# tin_of_fets.net
KiCad netlist of a schematic drawn in EAGLE
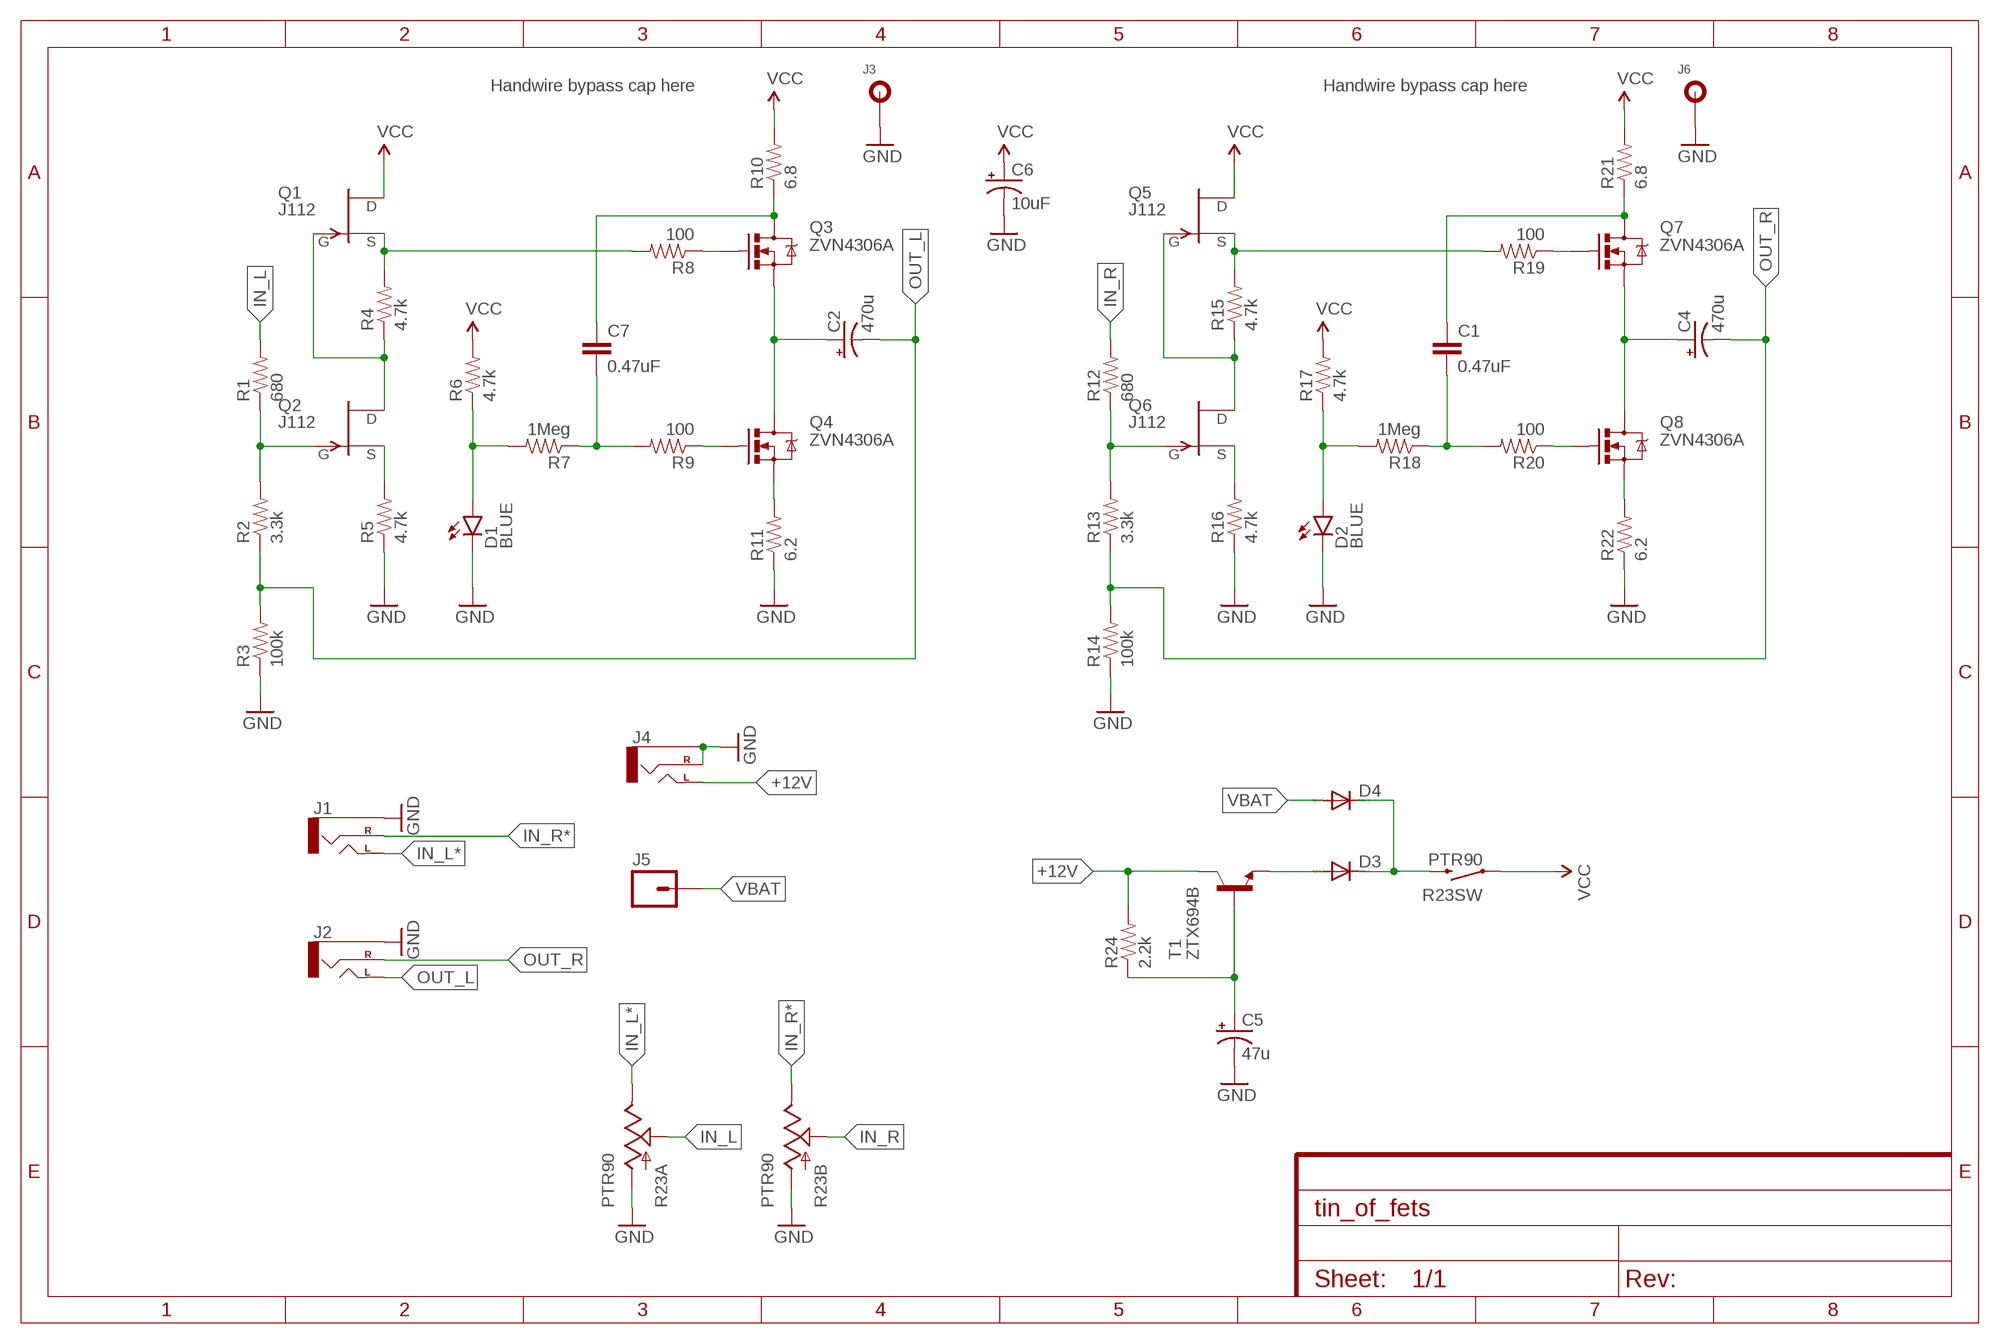
[diagram p0: schematic, sheet 1]

(export (version "E")
  (design (tool "Eeschema 10.0.6"))
  (components
    (comp (ref "A1")
      (value "9V-BATTERY-DOCU")
      (footprint "eagle-import:9V-BATTERY-DIM")
      (libsource (lib "eagle-import") (part "9V-BATTERY-DOCU"))
    )
    (comp (ref "A2")
      (value "9V-BATTERY-DOCU")
      (footprint "eagle-import:9V-BATTERY-DIM")
      (libsource (lib "eagle-import") (part "9V-BATTERY-DOCU"))
    )
    (comp (ref "A3")
      (value "ALTOIDS-DOCU")
      (footprint "eagle-import:ALTOIDS-INNER-DIM")
      (libsource (lib "eagle-import") (part "ALTOIDS-DOCU"))
    )
    (comp (ref "C1")
      (value "0.47uF")
      (footprint "eagle-import:C5B3.5")
      (libsource (lib "eagle-import") (part "C5/3.5"))
    )
    (comp (ref "C2")
      (value "470u")
      (footprint "eagle-import:CPOL-RADIAL-1000UF-25V")
      (libsource (lib "eagle-import") (part "CAP_POLPTH4"))
    )
    (comp (ref "C4")
      (value "470u")
      (footprint "eagle-import:CPOL-RADIAL-1000UF-25V")
      (libsource (lib "eagle-import") (part "CAP_POLPTH4"))
    )
    (comp (ref "C5")
      (value "47u")
      (footprint "eagle-import:CPOL-RADIAL-10UF-25V")
      (libsource (lib "eagle-import") (part "CAP_POLPTH2"))
    )
    (comp (ref "C6")
      (value "10uF")
      (footprint "eagle-import:CPOL-RADIAL-10UF-25V")
      (libsource (lib "eagle-import") (part "CAP_POLPTH2"))
    )
    (comp (ref "C7")
      (value "0.47uF")
      (footprint "eagle-import:C5B3.5")
      (libsource (lib "eagle-import") (part "C5/3.5"))
    )
    (comp (ref "D1")
      (value "BLUE")
      (footprint "eagle-import:LED3MM")
      (libsource (lib "eagle-import") (part "LED3MM"))
    )
    (comp (ref "D2")
      (value "BLUE")
      (footprint "eagle-import:LED3MM")
      (libsource (lib "eagle-import") (part "LED3MM"))
    )
    (comp (ref "D3")
      (value "DIODE-C1702-05")
      (footprint "eagle-import:C1702-05")
      (libsource (lib "eagle-import") (part "DIODE-C1702-05"))
    )
    (comp (ref "D4")
      (value "DIODE-C1702-05")
      (footprint "eagle-import:C1702-05")
      (libsource (lib "eagle-import") (part "DIODE-C1702-05"))
    )
    (comp (ref "J1")
      (value "AUDIO-JACK2.5MM")
      (footprint "eagle-import:STEREOJACK2.5MM_STEREOJACK2.5MM")
      (libsource (lib "eagle-import") (part "AUDIO-JACK2.5MM"))
    )
    (comp (ref "J2")
      (value "AUDIO-JACK2.5MM")
      (footprint "eagle-import:STEREOJACK2.5MM_STEREOJACK2.5MM")
      (libsource (lib "eagle-import") (part "AUDIO-JACK2.5MM"))
    )
    (comp (ref "J3")
      (value "PAD-NO-THERMAL")
      (footprint "eagle-import:PAD-NO-THERMAL")
      (libsource (lib "eagle-import") (part "PAD-NO-THERMAL"))
    )
    (comp (ref "J4")
      (value "AUDIO-JACK2.5MM")
      (footprint "eagle-import:STEREOJACK2.5MM_STEREOJACK2.5MM")
      (libsource (lib "eagle-import") (part "AUDIO-JACK2.5MM"))
    )
    (comp (ref "J5")
      (value "M01PTH")
      (footprint "eagle-import:1X01")
      (libsource (lib "eagle-import") (part "M01PTH"))
    )
    (comp (ref "J6")
      (value "PAD-NO-THERMAL")
      (footprint "eagle-import:PAD-NO-THERMAL")
      (libsource (lib "eagle-import") (part "PAD-NO-THERMAL"))
    )
    (comp (ref "Q1")
      (value "J112")
      (footprint "eagle-import:TO92")
      (libsource (lib "eagle-import") (part "?20J1"))
    )
    (comp (ref "Q2")
      (value "J112")
      (footprint "eagle-import:TO92")
      (libsource (lib "eagle-import") (part "?20J1"))
    )
    (comp (ref "Q3")
      (value "ZVN4306A")
      (footprint "eagle-import:TO-92")
      (libsource (lib "eagle-import") (part "MOSFET-NCHANNEL2N7000"))
    )
    (comp (ref "Q4")
      (value "ZVN4306A")
      (footprint "eagle-import:TO-92")
      (libsource (lib "eagle-import") (part "MOSFET-NCHANNEL2N7000"))
    )
    (comp (ref "Q5")
      (value "J112")
      (footprint "eagle-import:TO92")
      (libsource (lib "eagle-import") (part "?20J1"))
    )
    (comp (ref "Q6")
      (value "J112")
      (footprint "eagle-import:TO92")
      (libsource (lib "eagle-import") (part "?20J1"))
    )
    (comp (ref "Q7")
      (value "ZVN4306A")
      (footprint "eagle-import:TO-92")
      (libsource (lib "eagle-import") (part "MOSFET-NCHANNEL2N7000"))
    )
    (comp (ref "Q8")
      (value "ZVN4306A")
      (footprint "eagle-import:TO-92")
      (libsource (lib "eagle-import") (part "MOSFET-NCHANNEL2N7000"))
    )
    (comp (ref "R1")
      (value "680")
      (footprint "eagle-import:AXIAL-0.1-SM")
      (libsource (lib "eagle-import") (part "RESISTORPTH-1/4W-VERT-SM"))
    )
    (comp (ref "R2")
      (value "3.3k")
      (footprint "eagle-import:AXIAL-0.1-SM")
      (libsource (lib "eagle-import") (part "RESISTORPTH-1/4W-VERT-SM"))
    )
    (comp (ref "R3")
      (value "100k")
      (footprint "eagle-import:AXIAL-0.1-SM")
      (libsource (lib "eagle-import") (part "RESISTORPTH-1/4W-VERT-SM"))
    )
    (comp (ref "R4")
      (value "4.7k")
      (footprint "eagle-import:AXIAL-0.1-SM")
      (libsource (lib "eagle-import") (part "RESISTORPTH-1/4W-VERT-SM"))
    )
    (comp (ref "R5")
      (value "4.7k")
      (footprint "eagle-import:AXIAL-0.1-SM")
      (libsource (lib "eagle-import") (part "RESISTORPTH-1/4W-VERT-SM"))
    )
    (comp (ref "R6")
      (value "4.7k")
      (footprint "eagle-import:AXIAL-0.1-SM")
      (libsource (lib "eagle-import") (part "RESISTORPTH-1/4W-VERT-SM"))
    )
    (comp (ref "R7")
      (value "1Meg")
      (footprint "eagle-import:AXIAL-0.1-SM")
      (libsource (lib "eagle-import") (part "RESISTORPTH-1/4W-VERT-SM"))
    )
    (comp (ref "R8")
      (value "100")
      (footprint "eagle-import:AXIAL-0.1-SM")
      (libsource (lib "eagle-import") (part "RESISTORPTH-1/4W-VERT-SM"))
    )
    (comp (ref "R9")
      (value "100")
      (footprint "eagle-import:AXIAL-0.1-SM")
      (libsource (lib "eagle-import") (part "RESISTORPTH-1/4W-VERT-SM"))
    )
    (comp (ref "R10")
      (value "6.8")
      (footprint "eagle-import:AXIAL-0.1-SM")
      (libsource (lib "eagle-import") (part "RESISTORPTH-1/4W-VERT-SM"))
    )
    (comp (ref "R11")
      (value "6.2")
      (footprint "eagle-import:AXIAL-0.1-SM")
      (libsource (lib "eagle-import") (part "RESISTORPTH-1/4W-VERT-SM"))
    )
    (comp (ref "R12")
      (value "680")
      (footprint "eagle-import:AXIAL-0.1-SM")
      (libsource (lib "eagle-import") (part "RESISTORPTH-1/4W-VERT-SM"))
    )
    (comp (ref "R13")
      (value "3.3k")
      (footprint "eagle-import:AXIAL-0.1-SM")
      (libsource (lib "eagle-import") (part "RESISTORPTH-1/4W-VERT-SM"))
    )
    (comp (ref "R14")
      (value "100k")
      (footprint "eagle-import:AXIAL-0.1-SM")
      (libsource (lib "eagle-import") (part "RESISTORPTH-1/4W-VERT-SM"))
    )
    (comp (ref "R15")
      (value "4.7k")
      (footprint "eagle-import:AXIAL-0.1-SM")
      (libsource (lib "eagle-import") (part "RESISTORPTH-1/4W-VERT-SM"))
    )
    (comp (ref "R16")
      (value "4.7k")
      (footprint "eagle-import:AXIAL-0.1-SM")
      (libsource (lib "eagle-import") (part "RESISTORPTH-1/4W-VERT-SM"))
    )
    (comp (ref "R17")
      (value "4.7k")
      (footprint "eagle-import:AXIAL-0.1-SM")
      (libsource (lib "eagle-import") (part "RESISTORPTH-1/4W-VERT-SM"))
    )
    (comp (ref "R18")
      (value "1Meg")
      (footprint "eagle-import:AXIAL-0.1-SM")
      (libsource (lib "eagle-import") (part "RESISTORPTH-1/4W-VERT-SM"))
    )
    (comp (ref "R19")
      (value "100")
      (footprint "eagle-import:AXIAL-0.1-SM")
      (libsource (lib "eagle-import") (part "RESISTORPTH-1/4W-VERT-SM"))
    )
    (comp (ref "R20")
      (value "100")
      (footprint "eagle-import:AXIAL-0.1-SM")
      (libsource (lib "eagle-import") (part "RESISTORPTH-1/4W-VERT-SM"))
    )
    (comp (ref "R21")
      (value "6.8")
      (footprint "eagle-import:AXIAL-0.1-SM")
      (libsource (lib "eagle-import") (part "RESISTORPTH-1/4W-VERT-SM"))
    )
    (comp (ref "R22")
      (value "6.2")
      (footprint "eagle-import:AXIAL-0.1-SM")
      (libsource (lib "eagle-import") (part "RESISTORPTH-1/4W-VERT-SM"))
    )
    (comp (ref "R23")
      (value "PTR90")
      (footprint "eagle-import:PTR902")
      (libsource (lib "eagle-import") (part "PTR90"))
    )
    (comp (ref "R24")
      (value "2.2k")
      (footprint "eagle-import:AXIAL-0.1-SM")
      (libsource (lib "eagle-import") (part "RESISTORPTH-1/4W-VERT-SM"))
    )
    (comp (ref "T1")
      (value "ZTX694B")
      (footprint "eagle-import:TO92")
      (libsource (lib "eagle-import") (part "2N3565"))
    )
  )
  (nets
    (net (code "1") (name "+12V") (class "Default")
      (node (ref "J4") (pin "TIP1") (pinfunction "LEFT_TIP1") (pintype "bidirectional"))
      (node (ref "J4") (pin "TIP2") (pinfunction "LEFT_TIP2") (pintype "bidirectional"))
      (node (ref "R24") (pin "P$2") (pinfunction "2_P$2") (pintype "passive"))
      (node (ref "T1") (pin "1") (pinfunction "C_1") (pintype "passive"))
    )
    (net (code "2") (name "GND") (class "Default")
      (node (ref "C5") (pin "2") (pinfunction "-_2") (pintype "passive"))
      (node (ref "C6") (pin "2") (pinfunction "-_2") (pintype "passive"))
      (node (ref "D1") (pin "K") (pinfunction "C_K") (pintype "passive"))
      (node (ref "D2") (pin "K") (pinfunction "C_K") (pintype "passive"))
      (node (ref "J1") (pin "SHIELD") (pinfunction "SLEEVE_SHIELD") (pintype "bidirectional"))
      (node (ref "J2") (pin "SHIELD") (pinfunction "SLEEVE_SHIELD") (pintype "bidirectional"))
      (node (ref "J3") (pin "P$1") (pinfunction "P$1_P$1") (pintype "bidirectional"))
      (node (ref "J4") (pin "RING") (pinfunction "RIGHT_RING") (pintype "bidirectional"))
      (node (ref "J4") (pin "SHIELD") (pinfunction "SLEEVE_SHIELD") (pintype "bidirectional"))
      (node (ref "J6") (pin "P$1") (pinfunction "P$1_P$1") (pintype "bidirectional"))
      (node (ref "R11") (pin "P$1") (pinfunction "1_P$1") (pintype "passive"))
      (node (ref "R14") (pin "P$1") (pinfunction "1_P$1") (pintype "passive"))
      (node (ref "R16") (pin "P$1") (pinfunction "1_P$1") (pintype "passive"))
      (node (ref "R22") (pin "P$1") (pinfunction "1_P$1") (pintype "passive"))
      (node (ref "R23") (pin "R1.1") (pinfunction "A_R1.1") (pintype "passive"))
      (node (ref "R23") (pin "R2.1") (pinfunction "A_R2.1") (pintype "passive"))
      (node (ref "R3") (pin "P$1") (pinfunction "1_P$1") (pintype "passive"))
      (node (ref "R5") (pin "P$1") (pinfunction "1_P$1") (pintype "passive"))
    )
    (net (code "3") (name "IN_L") (class "Default")
      (node (ref "R1") (pin "P$2") (pinfunction "2_P$2") (pintype "passive"))
      (node (ref "R23") (pin "R1.2") (pinfunction "S_R1.2") (pintype "passive"))
    )
    (net (code "4") (name "IN_L*") (class "Default")
      (node (ref "J1") (pin "TIP1") (pinfunction "LEFT_TIP1") (pintype "bidirectional"))
      (node (ref "J1") (pin "TIP2") (pinfunction "LEFT_TIP2") (pintype "bidirectional"))
      (node (ref "R23") (pin "R1.3") (pinfunction "E_R1.3") (pintype "passive"))
    )
    (net (code "5") (name "IN_R") (class "Default")
      (node (ref "R12") (pin "P$2") (pinfunction "2_P$2") (pintype "passive"))
      (node (ref "R23") (pin "R2.2") (pinfunction "S_R2.2") (pintype "passive"))
    )
    (net (code "6") (name "IN_R*") (class "Default")
      (node (ref "J1") (pin "RING") (pinfunction "RIGHT_RING") (pintype "bidirectional"))
      (node (ref "R23") (pin "R2.3") (pinfunction "E_R2.3") (pintype "passive"))
    )
    (net (code "7") (name "Net-(C5-+)") (class "Default")
      (node (ref "C5") (pin "1") (pinfunction "+_1") (pintype "passive"))
      (node (ref "R24") (pin "P$1") (pinfunction "1_P$1") (pintype "passive"))
      (node (ref "T1") (pin "2") (pinfunction "B_2") (pintype "passive"))
    )
    (net (code "8") (name "Net-(Q1-G)") (class "Default")
      (node (ref "Q1") (pin "1") (pinfunction "G_1") (pintype "passive"))
      (node (ref "Q2") (pin "3") (pinfunction "D_3") (pintype "passive"))
      (node (ref "R4") (pin "P$1") (pinfunction "1_P$1") (pintype "passive"))
    )
    (net (code "9") (name "Net-(Q1-S)") (class "Default")
      (node (ref "Q1") (pin "2") (pinfunction "S_2") (pintype "passive"))
      (node (ref "R4") (pin "P$2") (pinfunction "2_P$2") (pintype "passive"))
      (node (ref "R8") (pin "P$2") (pinfunction "2_P$2") (pintype "passive"))
    )
    (net (code "10") (name "Net-(Q2-G)") (class "Default")
      (node (ref "Q2") (pin "1") (pinfunction "G_1") (pintype "passive"))
      (node (ref "R1") (pin "P$1") (pinfunction "1_P$1") (pintype "passive"))
      (node (ref "R2") (pin "P$2") (pinfunction "2_P$2") (pintype "passive"))
    )
    (net (code "11") (name "Net-(Q2-S)") (class "Default")
      (node (ref "Q2") (pin "2") (pinfunction "S_2") (pintype "passive"))
      (node (ref "R5") (pin "P$2") (pinfunction "2_P$2") (pintype "passive"))
    )
    (net (code "12") (name "Net-(Q3-D)") (class "Default")
      (node (ref "C7") (pin "1") (pinfunction "1_1") (pintype "passive"))
      (node (ref "Q3") (pin "3") (pinfunction "D_3") (pintype "passive"))
      (node (ref "R10") (pin "P$1") (pinfunction "1_P$1") (pintype "passive"))
    )
    (net (code "13") (name "Net-(Q3-G)") (class "Default")
      (node (ref "Q3") (pin "2") (pinfunction "G_2") (pintype "passive"))
      (node (ref "R8") (pin "P$1") (pinfunction "1_P$1") (pintype "passive"))
    )
    (net (code "14") (name "Net-(Q3-S)") (class "Default")
      (node (ref "C2") (pin "+") (pinfunction "+_+") (pintype "passive"))
      (node (ref "Q3") (pin "1") (pinfunction "S_1") (pintype "passive"))
      (node (ref "Q4") (pin "3") (pinfunction "D_3") (pintype "passive"))
    )
    (net (code "15") (name "Net-(Q4-G)") (class "Default")
      (node (ref "Q4") (pin "2") (pinfunction "G_2") (pintype "passive"))
      (node (ref "R9") (pin "P$1") (pinfunction "1_P$1") (pintype "passive"))
    )
    (net (code "16") (name "Net-(Q4-S)") (class "Default")
      (node (ref "Q4") (pin "1") (pinfunction "S_1") (pintype "passive"))
      (node (ref "R11") (pin "P$2") (pinfunction "2_P$2") (pintype "passive"))
    )
    (net (code "17") (name "Net-(Q5-G)") (class "Default")
      (node (ref "Q5") (pin "1") (pinfunction "G_1") (pintype "passive"))
      (node (ref "Q6") (pin "3") (pinfunction "D_3") (pintype "passive"))
      (node (ref "R15") (pin "P$1") (pinfunction "1_P$1") (pintype "passive"))
    )
    (net (code "18") (name "Net-(Q5-S)") (class "Default")
      (node (ref "Q5") (pin "2") (pinfunction "S_2") (pintype "passive"))
      (node (ref "R15") (pin "P$2") (pinfunction "2_P$2") (pintype "passive"))
      (node (ref "R19") (pin "P$2") (pinfunction "2_P$2") (pintype "passive"))
    )
    (net (code "19") (name "Net-(Q6-G)") (class "Default")
      (node (ref "Q6") (pin "1") (pinfunction "G_1") (pintype "passive"))
      (node (ref "R12") (pin "P$1") (pinfunction "1_P$1") (pintype "passive"))
      (node (ref "R13") (pin "P$2") (pinfunction "2_P$2") (pintype "passive"))
    )
    (net (code "20") (name "Net-(Q6-S)") (class "Default")
      (node (ref "Q6") (pin "2") (pinfunction "S_2") (pintype "passive"))
      (node (ref "R16") (pin "P$2") (pinfunction "2_P$2") (pintype "passive"))
    )
    (net (code "21") (name "Net-(Q7-D)") (class "Default")
      (node (ref "C1") (pin "1") (pinfunction "1_1") (pintype "passive"))
      (node (ref "Q7") (pin "3") (pinfunction "D_3") (pintype "passive"))
      (node (ref "R21") (pin "P$1") (pinfunction "1_P$1") (pintype "passive"))
    )
    (net (code "22") (name "Net-(Q7-G)") (class "Default")
      (node (ref "Q7") (pin "2") (pinfunction "G_2") (pintype "passive"))
      (node (ref "R19") (pin "P$1") (pinfunction "1_P$1") (pintype "passive"))
    )
    (net (code "23") (name "Net-(Q7-S)") (class "Default")
      (node (ref "C4") (pin "+") (pinfunction "+_+") (pintype "passive"))
      (node (ref "Q7") (pin "1") (pinfunction "S_1") (pintype "passive"))
      (node (ref "Q8") (pin "3") (pinfunction "D_3") (pintype "passive"))
    )
    (net (code "24") (name "Net-(Q8-G)") (class "Default")
      (node (ref "Q8") (pin "2") (pinfunction "G_2") (pintype "passive"))
      (node (ref "R20") (pin "P$1") (pinfunction "1_P$1") (pintype "passive"))
    )
    (net (code "25") (name "Net-(Q8-S)") (class "Default")
      (node (ref "Q8") (pin "1") (pinfunction "S_1") (pintype "passive"))
      (node (ref "R22") (pin "P$2") (pinfunction "2_P$2") (pintype "passive"))
    )
    (net (code "26") (name "Net-(R6-1)") (class "Default")
      (node (ref "D1") (pin "A") (pinfunction "A_A") (pintype "passive"))
      (node (ref "R6") (pin "P$1") (pinfunction "1_P$1") (pintype "passive"))
      (node (ref "R7") (pin "P$2") (pinfunction "2_P$2") (pintype "passive"))
    )
    (net (code "27") (name "Net-(R7-1)") (class "Default")
      (node (ref "C7") (pin "2") (pinfunction "2_2") (pintype "passive"))
      (node (ref "R7") (pin "P$1") (pinfunction "1_P$1") (pintype "passive"))
      (node (ref "R9") (pin "P$2") (pinfunction "2_P$2") (pintype "passive"))
    )
    (net (code "28") (name "Net-(R17-1)") (class "Default")
      (node (ref "D2") (pin "A") (pinfunction "A_A") (pintype "passive"))
      (node (ref "R17") (pin "P$1") (pinfunction "1_P$1") (pintype "passive"))
      (node (ref "R18") (pin "P$2") (pinfunction "2_P$2") (pintype "passive"))
    )
    (net (code "29") (name "Net-(R18-1)") (class "Default")
      (node (ref "C1") (pin "2") (pinfunction "2_2") (pintype "passive"))
      (node (ref "R18") (pin "P$1") (pinfunction "1_P$1") (pintype "passive"))
      (node (ref "R20") (pin "P$2") (pinfunction "2_P$2") (pintype "passive"))
    )
    (net (code "30") (name "Net-(R23C-2)") (class "Default")
      (node (ref "D3") (pin "C") (pinfunction "C_C") (pintype "passive"))
      (node (ref "D4") (pin "C") (pinfunction "C_C") (pintype "passive"))
      (node (ref "R23") (pin "SW2") (pinfunction "2_SW2") (pintype "passive"))
    )
    (net (code "31") (name "Net-(T1-E)") (class "Default")
      (node (ref "D3") (pin "A") (pinfunction "A_A") (pintype "passive"))
      (node (ref "T1") (pin "3") (pinfunction "E_3") (pintype "passive"))
    )
    (net (code "32") (name "OUT_L") (class "Default")
      (node (ref "C2") (pin "-") (pinfunction "-_-") (pintype "passive"))
      (node (ref "J2") (pin "TIP1") (pinfunction "LEFT_TIP1") (pintype "bidirectional"))
      (node (ref "J2") (pin "TIP2") (pinfunction "LEFT_TIP2") (pintype "bidirectional"))
      (node (ref "R2") (pin "P$1") (pinfunction "1_P$1") (pintype "passive"))
      (node (ref "R3") (pin "P$2") (pinfunction "2_P$2") (pintype "passive"))
    )
    (net (code "33") (name "OUT_R") (class "Default")
      (node (ref "C4") (pin "-") (pinfunction "-_-") (pintype "passive"))
      (node (ref "J2") (pin "RING") (pinfunction "RIGHT_RING") (pintype "bidirectional"))
      (node (ref "R13") (pin "P$1") (pinfunction "1_P$1") (pintype "passive"))
      (node (ref "R14") (pin "P$2") (pinfunction "2_P$2") (pintype "passive"))
    )
    (net (code "34") (name "VBAT") (class "Default")
      (node (ref "D4") (pin "A") (pinfunction "A_A") (pintype "passive"))
      (node (ref "J5") (pin "1") (pinfunction "1_1") (pintype "passive"))
    )
    (net (code "35") (name "VCC") (class "Default")
      (node (ref "C6") (pin "1") (pinfunction "+_1") (pintype "passive"))
      (node (ref "Q1") (pin "3") (pinfunction "D_3") (pintype "passive"))
      (node (ref "Q5") (pin "3") (pinfunction "D_3") (pintype "passive"))
      (node (ref "R10") (pin "P$2") (pinfunction "2_P$2") (pintype "passive"))
      (node (ref "R17") (pin "P$2") (pinfunction "2_P$2") (pintype "passive"))
      (node (ref "R21") (pin "P$2") (pinfunction "2_P$2") (pintype "passive"))
      (node (ref "R23") (pin "SW1") (pinfunction "1_SW1") (pintype "passive"))
      (node (ref "R6") (pin "P$2") (pinfunction "2_P$2") (pintype "passive"))
    )
  )
)
